# EDU_High-Speed-Design_CPU_SATA.net
KiCad netlist of a schematic drawn in Altium Designer
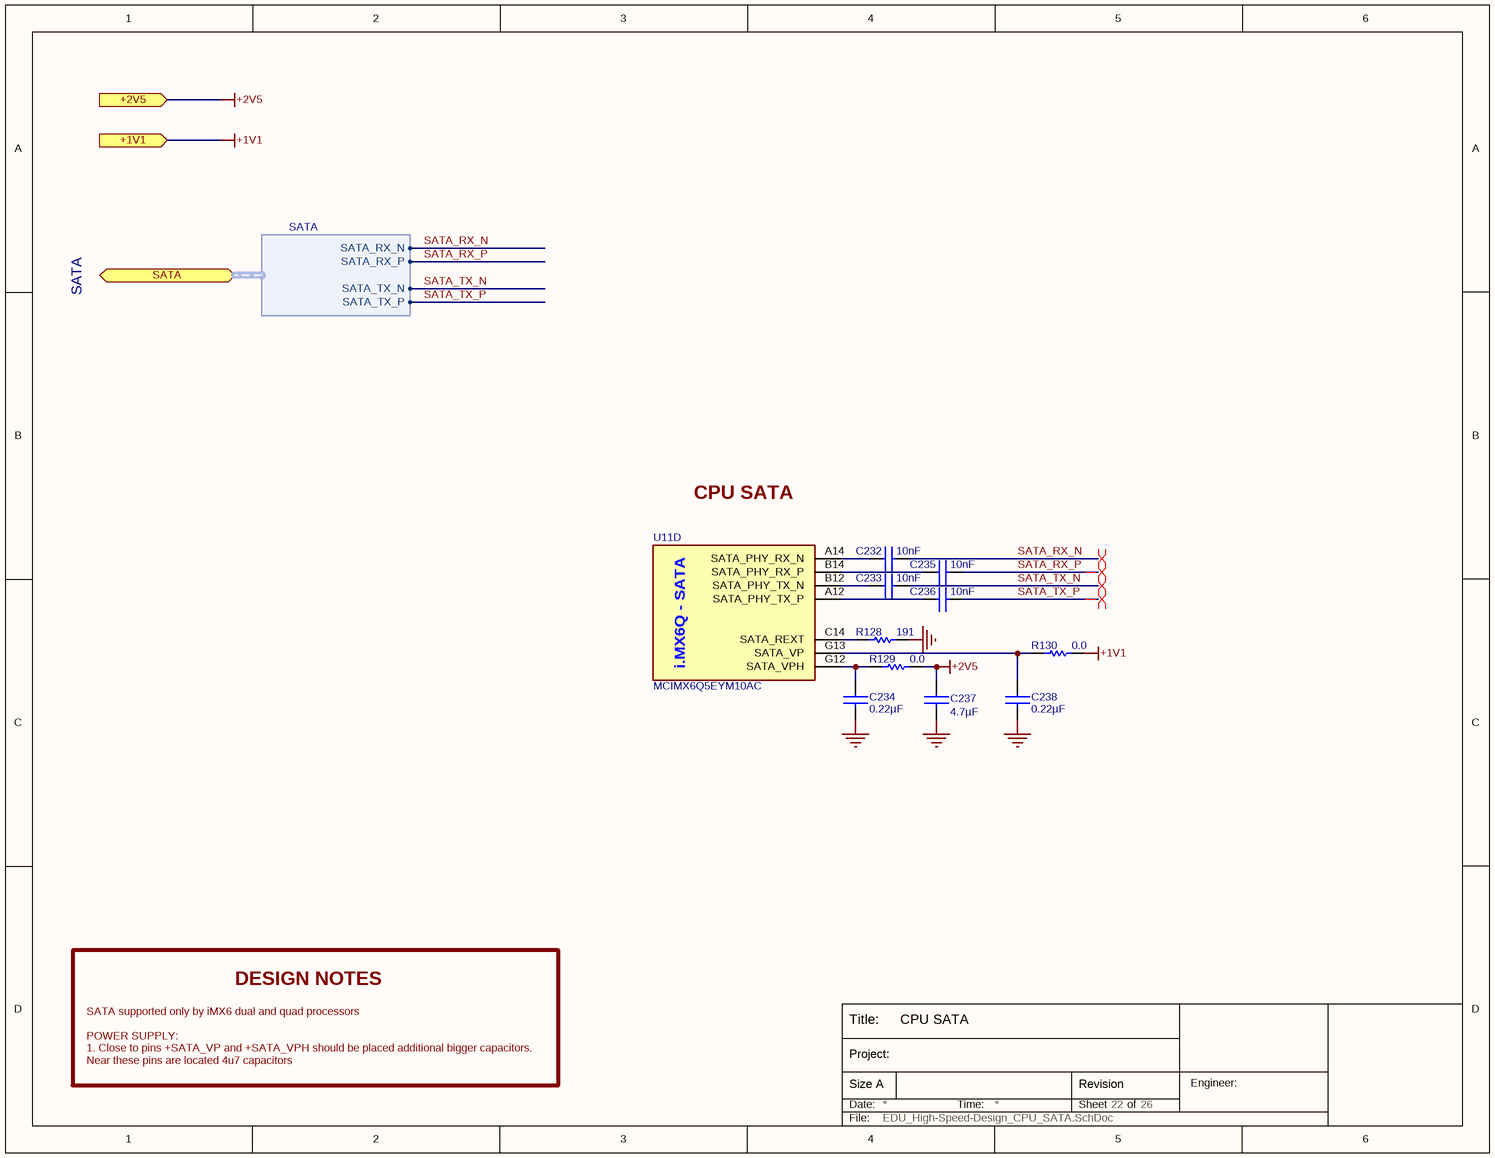
[diagram p0: EDU_High-Speed-Design_CPU_SATA.SchDoc]

(export (version "E")
  (design (tool "Eeschema 10.0.6"))
  (components
    (comp (ref "C232")
      (value "10nF")
      (footprint "C0402")
      (description "CAP CER 10000PF 50V 10% X7R 0402")
      (fields
        (field (name "MANUFACTURER") "TDK Corporation")
        (field (name "MANUFACTURER PART NUMBER") "C1005X7R1H103K")
      )
      (libsource (lib "EDU_High-Speed-Design") (part "C1005X7R1H103K"))
    )
    (comp (ref "C233")
      (value "10nF")
      (footprint "C0402")
      (description "CAP CER 10000PF 50V 10% X7R 0402")
      (fields
        (field (name "MANUFACTURER") "TDK Corporation")
        (field (name "MANUFACTURER PART NUMBER") "C1005X7R1H103K")
      )
      (libsource (lib "EDU_High-Speed-Design") (part "C1005X7R1H103K"))
    )
    (comp (ref "C234")
      (value "0.22µF")
      (footprint "C0402")
      (description "CAP CER .22UF 25V X5R 20% 0402")
      (fields (field (name "VOLTAGE") "25V"))
      (libsource (lib "EDU_High-Speed-Design") (part "C1005X5R1E224M"))
    )
    (comp (ref "C235")
      (value "10nF")
      (footprint "C0402")
      (description "CAP CER 10000PF 50V 10% X7R 0402")
      (fields
        (field (name "MANUFACTURER") "TDK Corporation")
        (field (name "MANUFACTURER PART NUMBER") "C1005X7R1H103K")
      )
      (libsource (lib "EDU_High-Speed-Design") (part "C1005X7R1H103K"))
    )
    (comp (ref "C236")
      (value "10nF")
      (footprint "C0402")
      (description "CAP CER 10000PF 50V 10% X7R 0402")
      (fields
        (field (name "MANUFACTURER") "TDK Corporation")
        (field (name "MANUFACTURER PART NUMBER") "C1005X7R1H103K")
      )
      (libsource (lib "EDU_High-Speed-Design") (part "C1005X7R1H103K"))
    )
    (comp (ref "C237")
      (value "4.7µF")
      (footprint "C0402")
      (description "CAP CER 4.7UF 10V 20% X5R 0402")
      (fields (field (name "VOLTAGE") "10V"))
      (libsource (lib "EDU_High-Speed-Design") (part "C1005X5R1A475M"))
    )
    (comp (ref "C238")
      (value "0.22µF")
      (footprint "C0402")
      (description "CAP CER .22UF 25V X5R 20% 0402")
      (fields (field (name "VOLTAGE") "25V"))
      (libsource (lib "EDU_High-Speed-Design") (part "C1005X5R1E224M"))
    )
    (comp (ref "R128")
      (value "191")
      (footprint "R0402")
      (description "RES 191 OHM 1/16W 1% 0402 SMD")
      (fields
        (field (name "MANUFACTURER") "Vishay Dale")
        (field (name "MANUFACTURER PART NUMBER") "CRCW0402191RFKED")
      )
      (libsource (lib "EDU_High-Speed-Design") (part "CRCW0402191RFKED"))
    )
    (comp (ref "R129")
      (value "0.0")
      (footprint "R0402")
      (description "RES 0.0 OHM 1/16W 0402 SMD")
      (libsource (lib "EDU_High-Speed-Design") (part "RC0402JR-070RL"))
    )
    (comp (ref "R130")
      (value "0.0")
      (footprint "R0402")
      (description "RES 0.0 OHM 1/16W 0402 SMD")
      (libsource (lib "EDU_High-Speed-Design") (part "RC0402JR-070RL"))
    )
    (comp (ref "U11")
      (value "MCIMX6Q5EYM10AC")
      (footprint "MCIMX6Q5EYM10AC")
      (description "IC MCU 32BIT ARM QUAD 624FCBGA")
      (libsource (lib "EDU_High-Speed-Design") (part "MCIMX6Q5EYM10AC"))
    )
  )
  (nets
    (net (code "2") (name "+1V1") (class "Default")
      (node (ref "R130") (pin "2") (pinfunction "2_2") (pintype "passive"))
    )
    (net (code "3") (name "+2V5") (class "Default")
      (node (ref "C237") (pin "1") (pinfunction "1_1") (pintype "passive"))
      (node (ref "R129") (pin "2") (pinfunction "2_2") (pintype "passive"))
    )
    (net (code "4") (name "/SATA_RX_N") (class "Default")
      (node (ref "C232") (pin "2") (pinfunction "2_2") (pintype "passive"))
    )
    (net (code "5") (name "/SATA_RX_P") (class "Default")
      (node (ref "C235") (pin "2") (pinfunction "2_2") (pintype "passive"))
    )
    (net (code "6") (name "/SATA_TX_N") (class "Default")
      (node (ref "C233") (pin "2") (pinfunction "2_2") (pintype "passive"))
    )
    (net (code "7") (name "/SATA_TX_P") (class "Default")
      (node (ref "C236") (pin "2") (pinfunction "2_2") (pintype "passive"))
    )
    (net (code "9") (name "GND") (class "Default")
      (node (ref "C234") (pin "2") (pinfunction "2_2") (pintype "passive"))
      (node (ref "C237") (pin "2") (pinfunction "2_2") (pintype "passive"))
      (node (ref "C238") (pin "2") (pinfunction "2_2") (pintype "passive"))
      (node (ref "R128") (pin "1") (pinfunction "1_1") (pintype "passive"))
    )
    (net (code "10") (name "Net-(U11D-SATA_PHY_RX_N)") (class "Default")
      (node (ref "C232") (pin "1") (pinfunction "1_1") (pintype "passive"))
      (node (ref "U11") (pin "A14") (pinfunction "SATA_PHY_RX_N_A14") (pintype "passive"))
    )
    (net (code "11") (name "Net-(U11D-SATA_PHY_RX_P)") (class "Default")
      (node (ref "C235") (pin "1") (pinfunction "1_1") (pintype "passive"))
      (node (ref "U11") (pin "B14") (pinfunction "SATA_PHY_RX_P_B14") (pintype "passive"))
    )
    (net (code "12") (name "Net-(U11D-SATA_PHY_TX_N)") (class "Default")
      (node (ref "C233") (pin "1") (pinfunction "1_1") (pintype "passive"))
      (node (ref "U11") (pin "B12") (pinfunction "SATA_PHY_TX_N_B12") (pintype "passive"))
    )
    (net (code "13") (name "Net-(U11D-SATA_PHY_TX_P)") (class "Default")
      (node (ref "C236") (pin "1") (pinfunction "1_1") (pintype "passive"))
      (node (ref "U11") (pin "A12") (pinfunction "SATA_PHY_TX_P_A12") (pintype "passive"))
    )
    (net (code "14") (name "Net-(U11D-SATA_REXT)") (class "Default")
      (node (ref "R128") (pin "2") (pinfunction "2_2") (pintype "passive"))
      (node (ref "U11") (pin "C14") (pinfunction "SATA_REXT_C14") (pintype "passive"))
    )
    (net (code "15") (name "Net-(U11D-SATA_VP)") (class "Default")
      (node (ref "C238") (pin "1") (pinfunction "1_1") (pintype "passive"))
      (node (ref "R130") (pin "1") (pinfunction "1_1") (pintype "passive"))
      (node (ref "U11") (pin "G13") (pinfunction "SATA_VP_G13") (pintype "passive"))
    )
    (net (code "16") (name "Net-(U11D-SATA_VPH)") (class "Default")
      (node (ref "C234") (pin "1") (pinfunction "1_1") (pintype "passive"))
      (node (ref "R129") (pin "1") (pinfunction "1_1") (pintype "passive"))
      (node (ref "U11") (pin "G12") (pinfunction "SATA_VPH_G12") (pintype "passive"))
    )
  )
)
